# SCH.net
KiCad netlist of a schematic drawn in Altium Designer
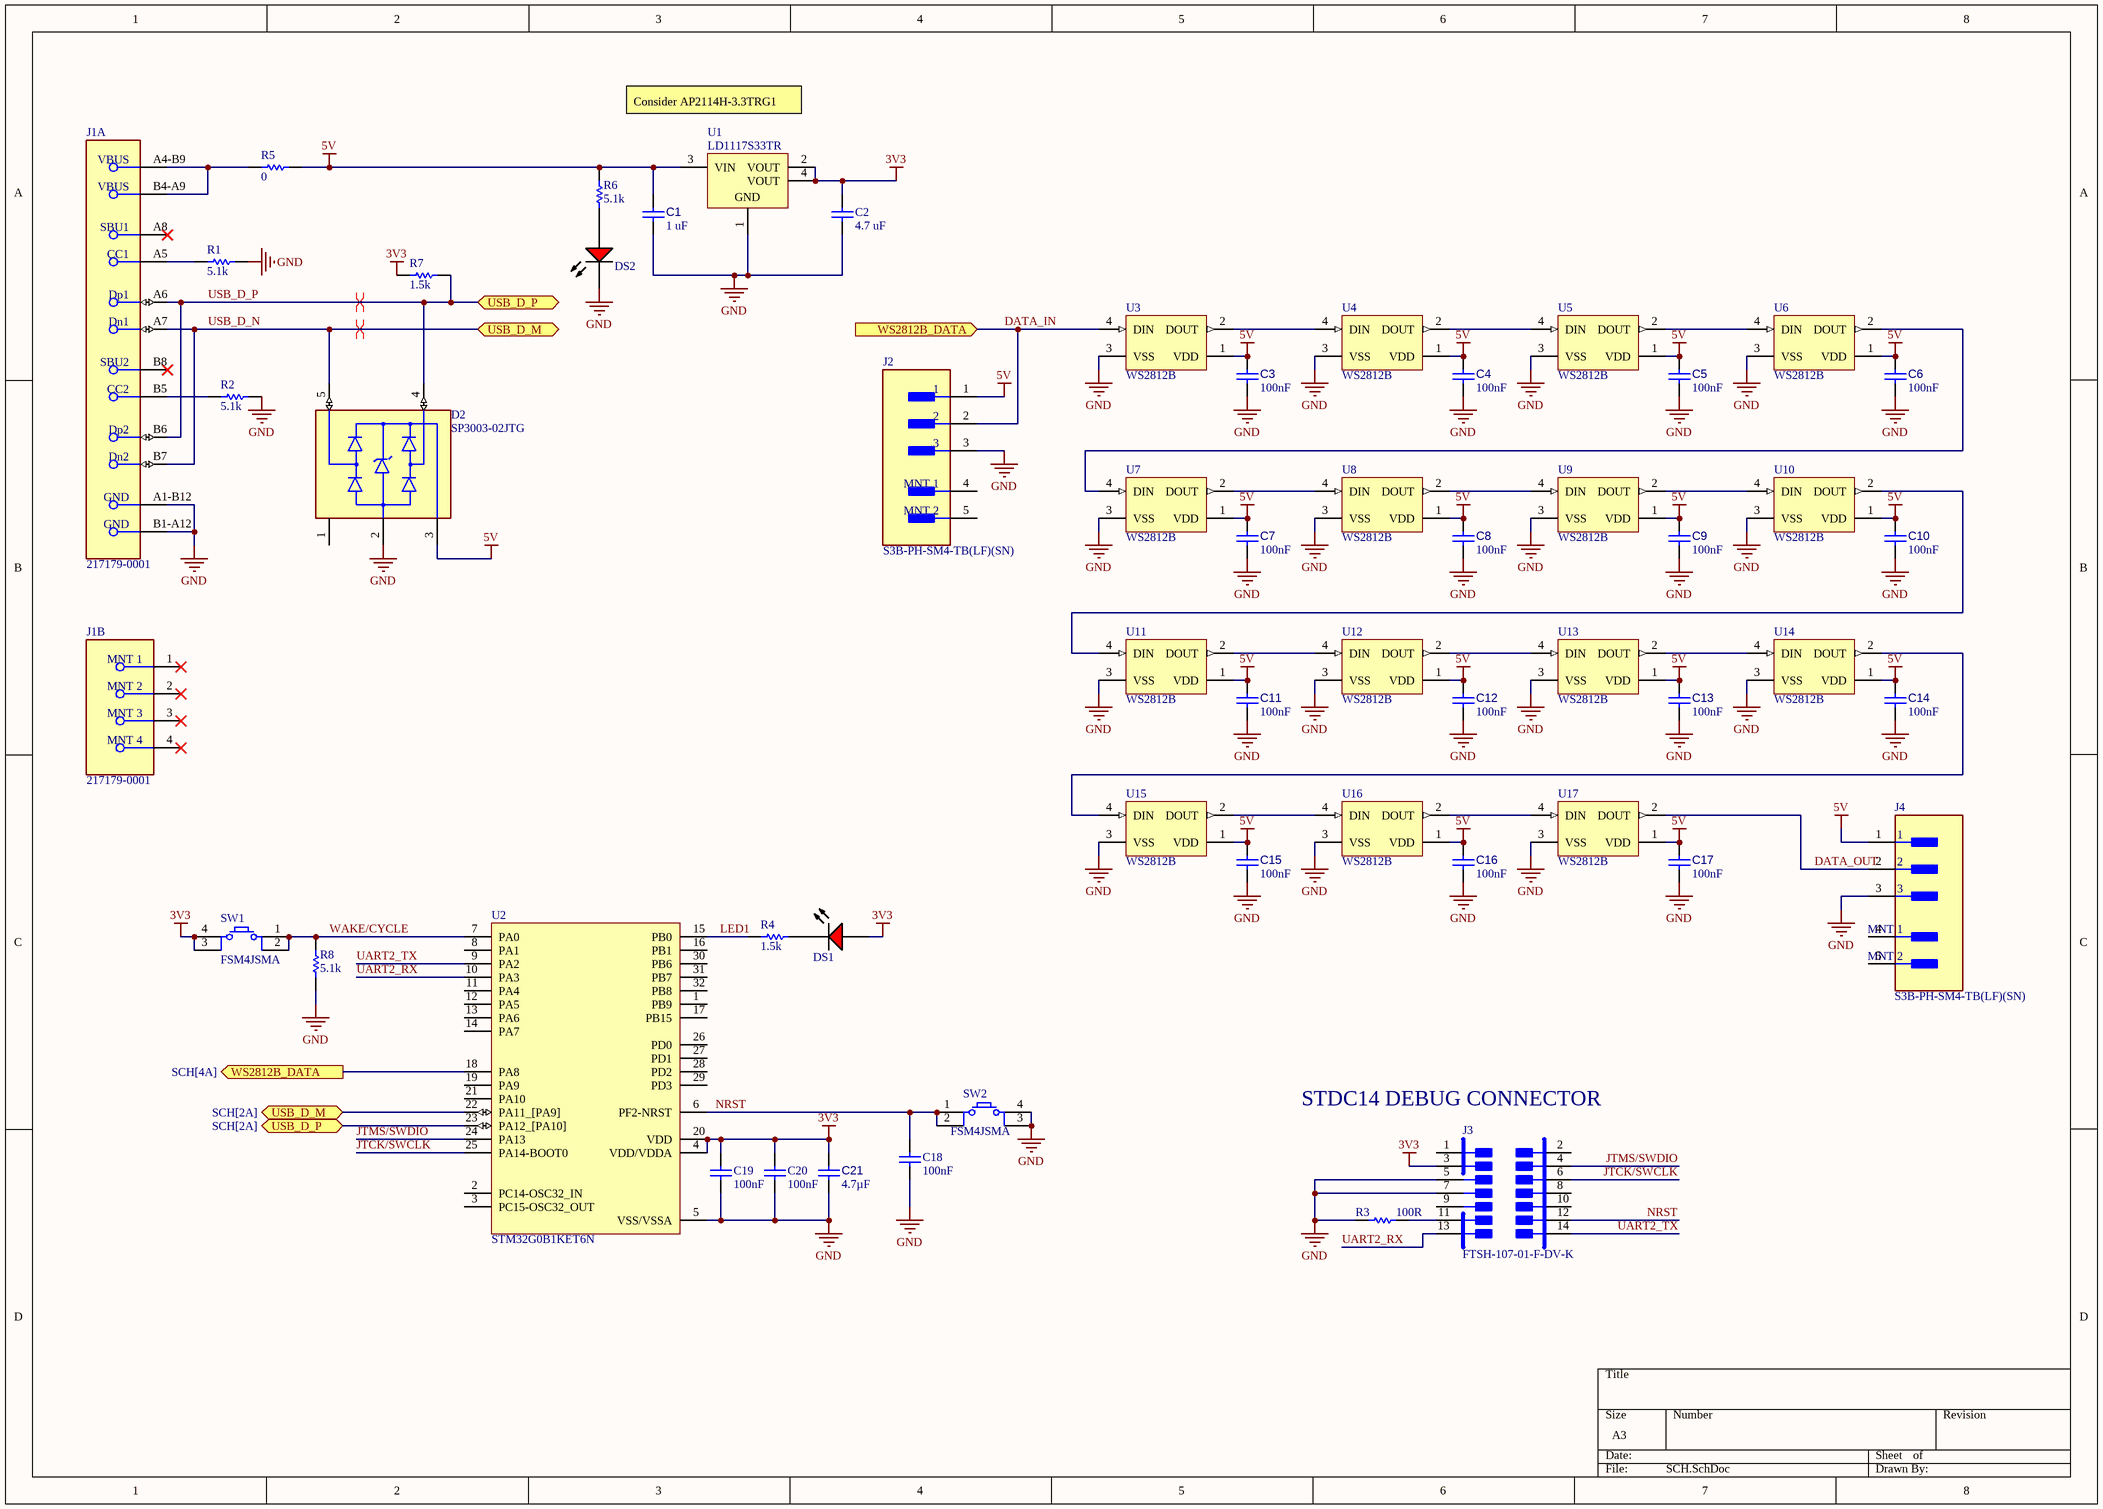
[diagram p0: SCH.SchDoc]

(export (version "E")
  (design (tool "Eeschema 10.0.6"))
  (components
    (comp (ref "C1")
      (value "1 uF")
      (footprint "CAPC3216X19M")
      (description "CAP CER 1UF 100V X7R 1206")
      (fields (field (name "TOLERANCE") "+/-10%") (field (name "Comment") "Capacitor 1 uF +/-10% 100V 1206"))
      (libsource (lib "Dalhousie Formula SAE") (part "CAP-NP-2"))
    )
    (comp (ref "C2")
      (value "4.7 uF")
      (footprint "CAPC3216X19M")
      (description "CAP CER 4.7UF 50V X7R 1206")
      (fields (field (name "TOLERANCE") "+/-10%") (field (name "Comment") "Capacitor 4.7 uF +/-10% 50V 1206"))
      (libsource (lib "Dalhousie Formula SAE") (part "CAP-NP-2"))
    )
    (comp (ref "C3")
      (value "100nF")
      (footprint "CAPC1609X09M")
      (description "CAP CER 0.1UF 50V X7R 0603")
      (fields (field (name "TOLERANCE") "10%") (field (name "Comment") "Capacitor 0.1 uF 10 % 50V 0603"))
      (libsource (lib "Dalhousie Formula SAE") (part "CAP-NP-2"))
    )
    (comp (ref "C4")
      (value "100nF")
      (footprint "CAPC1609X09M")
      (description "CAP CER 0.1UF 50V X7R 0603")
      (fields (field (name "TOLERANCE") "10%") (field (name "Comment") "Capacitor 0.1 uF 10 % 50V 0603"))
      (libsource (lib "Dalhousie Formula SAE") (part "CAP-NP-2"))
    )
    (comp (ref "C5")
      (value "100nF")
      (footprint "CAPC1609X09M")
      (description "CAP CER 0.1UF 50V X7R 0603")
      (fields (field (name "TOLERANCE") "10%") (field (name "Comment") "Capacitor 0.1 uF 10 % 50V 0603"))
      (libsource (lib "Dalhousie Formula SAE") (part "CAP-NP-2"))
    )
    (comp (ref "C6")
      (value "100nF")
      (footprint "CAPC1609X09M")
      (description "CAP CER 0.1UF 50V X7R 0603")
      (fields (field (name "TOLERANCE") "10%") (field (name "Comment") "Capacitor 0.1 uF 10 % 50V 0603"))
      (libsource (lib "Dalhousie Formula SAE") (part "CAP-NP-2"))
    )
    (comp (ref "C7")
      (value "100nF")
      (footprint "CAPC1609X09M")
      (description "CAP CER 0.1UF 50V X7R 0603")
      (fields (field (name "TOLERANCE") "10%") (field (name "Comment") "Capacitor 0.1 uF 10 % 50V 0603"))
      (libsource (lib "Dalhousie Formula SAE") (part "CAP-NP-2"))
    )
    (comp (ref "C8")
      (value "100nF")
      (footprint "CAPC1609X09M")
      (description "CAP CER 0.1UF 50V X7R 0603")
      (fields (field (name "TOLERANCE") "10%") (field (name "Comment") "Capacitor 0.1 uF 10 % 50V 0603"))
      (libsource (lib "Dalhousie Formula SAE") (part "CAP-NP-2"))
    )
    (comp (ref "C9")
      (value "100nF")
      (footprint "CAPC1609X09M")
      (description "CAP CER 0.1UF 50V X7R 0603")
      (fields (field (name "TOLERANCE") "10%") (field (name "Comment") "Capacitor 0.1 uF 10 % 50V 0603"))
      (libsource (lib "Dalhousie Formula SAE") (part "CAP-NP-2"))
    )
    (comp (ref "C10")
      (value "100nF")
      (footprint "CAPC1609X09M")
      (description "CAP CER 0.1UF 50V X7R 0603")
      (fields (field (name "TOLERANCE") "10%") (field (name "Comment") "Capacitor 0.1 uF 10 % 50V 0603"))
      (libsource (lib "Dalhousie Formula SAE") (part "CAP-NP-2"))
    )
    (comp (ref "C11")
      (value "100nF")
      (footprint "CAPC1609X09M")
      (description "CAP CER 0.1UF 50V X7R 0603")
      (fields (field (name "TOLERANCE") "10%") (field (name "Comment") "Capacitor 0.1 uF 10 % 50V 0603"))
      (libsource (lib "Dalhousie Formula SAE") (part "CAP-NP-2"))
    )
    (comp (ref "C12")
      (value "100nF")
      (footprint "CAPC1609X09M")
      (description "CAP CER 0.1UF 50V X7R 0603")
      (fields (field (name "TOLERANCE") "10%") (field (name "Comment") "Capacitor 0.1 uF 10 % 50V 0603"))
      (libsource (lib "Dalhousie Formula SAE") (part "CAP-NP-2"))
    )
    (comp (ref "C13")
      (value "100nF")
      (footprint "CAPC1609X09M")
      (description "CAP CER 0.1UF 50V X7R 0603")
      (fields (field (name "TOLERANCE") "10%") (field (name "Comment") "Capacitor 0.1 uF 10 % 50V 0603"))
      (libsource (lib "Dalhousie Formula SAE") (part "CAP-NP-2"))
    )
    (comp (ref "C14")
      (value "100nF")
      (footprint "CAPC1609X09M")
      (description "CAP CER 0.1UF 50V X7R 0603")
      (fields (field (name "TOLERANCE") "10%") (field (name "Comment") "Capacitor 0.1 uF 10 % 50V 0603"))
      (libsource (lib "Dalhousie Formula SAE") (part "CAP-NP-2"))
    )
    (comp (ref "C15")
      (value "100nF")
      (footprint "CAPC1609X09M")
      (description "CAP CER 0.1UF 50V X7R 0603")
      (fields (field (name "TOLERANCE") "10%") (field (name "Comment") "Capacitor 0.1 uF 10 % 50V 0603"))
      (libsource (lib "Dalhousie Formula SAE") (part "CAP-NP-2"))
    )
    (comp (ref "C16")
      (value "100nF")
      (footprint "CAPC1609X09M")
      (description "CAP CER 0.1UF 50V X7R 0603")
      (fields (field (name "TOLERANCE") "10%") (field (name "Comment") "Capacitor 0.1 uF 10 % 50V 0603"))
      (libsource (lib "Dalhousie Formula SAE") (part "CAP-NP-2"))
    )
    (comp (ref "C17")
      (value "100nF")
      (footprint "CAPC1609X09M")
      (description "CAP CER 0.1UF 50V X7R 0603")
      (fields (field (name "TOLERANCE") "10%") (field (name "Comment") "Capacitor 0.1 uF 10 % 50V 0603"))
      (libsource (lib "Dalhousie Formula SAE") (part "CAP-NP-2"))
    )
    (comp (ref "C18")
      (value "100nF")
      (footprint "CAPC1609X09M")
      (description "CAP CER 0.1UF 50V X7R 0603")
      (fields (field (name "TOLERANCE") "10%") (field (name "Comment") "Capacitor 0.1 uF 10 % 50V 0603"))
      (libsource (lib "Dalhousie Formula SAE") (part "CAP-NP-2"))
    )
    (comp (ref "C19")
      (value "100nF")
      (footprint "CAPC1609X09M")
      (description "CAP CER 0.1UF 50V X7R 0603")
      (fields (field (name "TOLERANCE") "10%") (field (name "Comment") "Capacitor 0.1 uF 10 % 50V 0603"))
      (libsource (lib "Dalhousie Formula SAE") (part "CAP-NP-2"))
    )
    (comp (ref "C20")
      (value "100nF")
      (footprint "CAPC1609X09M")
      (description "CAP CER 0.1UF 50V X7R 0603")
      (fields (field (name "TOLERANCE") "10%") (field (name "Comment") "Capacitor 0.1 uF 10 % 50V 0603"))
      (libsource (lib "Dalhousie Formula SAE") (part "CAP-NP-2"))
    )
    (comp (ref "C21")
      (value "4.7µF")
      (footprint "CAPC1609X09M")
      (description "CAP CER 4.7UF 35V X5R 0603")
      (fields (field (name "TOLERANCE") "10%") (field (name "Comment") "Capacitor 4.7 uF 10 % 35V 0603"))
      (libsource (lib "Dalhousie Formula SAE") (part "CAP-NP-2"))
    )
    (comp (ref "D2")
      (value "SP3003-02JTG")
      (footprint "FP-SP3003-02JTG-MFG")
      (description "TVS DIODE 6V 15V SC70-5")
      (fields
        (field (name "OCTOPART") "https://octopart.com/sp3003-02jtg-littelfuse-11540566")
        (field (name "MANUFACTURER") "Littelfuse")
      )
      (libsource (lib "Altium Content Vault") (part "04e8c59ec1a98fd1540dbf4f650d9d1"))
    )
    (comp (ref "DS1")
      (value "19-217/R6C-AL1M2VY/3T")
      (footprint "EVRL-0603-2_V")
      (description "Chip LED, Red, 5 V, 25 mA, -40 to 85 degC, 2-Pin SMD (0603), RoHS, Tape and Reel")
      (fields (field (name "MANUFACTURER") "Everlight Electronics"))
      (libsource (lib "Dalhousie Formula SAE") (part "LED-RED-AK-2"))
    )
    (comp (ref "DS2")
      (value "19-217/R6C-AL1M2VY/3T")
      (footprint "EVRL-0603-2_V")
      (description "Chip LED, Red, 5 V, 25 mA, -40 to 85 degC, 2-Pin SMD (0603), RoHS, Tape and Reel")
      (fields (field (name "MANUFACTURER") "Everlight Electronics"))
      (libsource (lib "Dalhousie Formula SAE") (part "LED-RED-AK-2"))
    )
    (comp (ref "J1")
      (value "217179-0001")
      (footprint "FP-2171790001-MFG")
      (description "CONN RCP USB2.0 TYP C 24P SMD RA")
      (libsource (lib "Altium Content Vault") (part "8b86497a633d14b3f74642136fc0ce6"))
    )
    (comp (ref "J2")
      (value "S3B-PH-SM4-TB(LF)(SN)")
      (footprint "FP-S3B-PH-SM4-TB_LF_SN-MFG")
      (description "CONN HEADER SMD R/A 3POS 2MM")
      (libsource (lib "") (part "38689d6f3df0f9b234c6ddcef280d85_1"))
    )
    (comp (ref "J3")
      (value "FTSH-107-01-F-DV-K")
      (footprint "FP-FTSH-107-01-F-DV-K-MFG")
      (libsource (lib "Dalhousie Formula SAE") (part "ab214579d66ef07f87fa9c6f4e4f9ab"))
    )
    (comp (ref "J4")
      (value "S3B-PH-SM4-TB(LF)(SN)")
      (footprint "FP-S3B-PH-SM4-TB_LF_SN-MFG")
      (description "CONN HEADER SMD R/A 3POS 2MM")
      (libsource (lib "Altium Content Vault") (part "38689d6f3df0f9b234c6ddcef280d85"))
    )
    (comp (ref "R1")
      (value "5.1k")
      (footprint "RESC1608X55X25ML10T15")
      (description "0603 (1608 Metric) 1/10 W 5K1 1 Thick Film Chip Resistor")
      (fields (field (name "TOLERANCE") "1%") (field (name "POWER") "100mW"))
      (libsource (lib "Dalhousie Formula SAE") (part "RES-2"))
    )
    (comp (ref "R2")
      (value "5.1k")
      (footprint "RESC1608X55X25ML10T15")
      (description "0603 (1608 Metric) 1/10 W 5K1 1 Thick Film Chip Resistor")
      (fields (field (name "TOLERANCE") "1%") (field (name "POWER") "100mW"))
      (libsource (lib "Dalhousie Formula SAE") (part "RES-2"))
    )
    (comp (ref "R3")
      (value "100R")
      (footprint "RESC1608X55X25ML10T15")
      (description "0603 (1608 Metric) 1/10 W 100R 1 Thick Film Chip Resistor")
      (fields (field (name "POWER") "100mW") (field (name "TOLERANCE") "1%"))
      (libsource (lib "Dalhousie Formula SAE") (part "RES-2"))
    )
    (comp (ref "R4")
      (value "1.5k")
      (footprint "RESC1608X55X25ML10T15")
      (description "0603 (1608 Metric) 1/10 W 1K5 1 Thick Film Chip Resistor")
      (fields (field (name "TOLERANCE") "1%") (field (name "POWER") "100mW"))
      (libsource (lib "Dalhousie Formula SAE") (part "RES-2"))
    )
    (comp (ref "R5")
      (value "0")
      (footprint "RESC3116X70X50ML13T20")
      (description "Jumper 1206 (3216 Metric)")
      (fields (field (name "POWER") "250mW") (field (name "TOLERANCE") "0%"))
      (libsource (lib "Dalhousie Formula SAE") (part "RES-2"))
    )
    (comp (ref "R6")
      (value "5.1k")
      (footprint "RESC1608X55X25ML10T15")
      (description "0603 (1608 Metric) 1/10 W 5K1 1 Thick Film Chip Resistor")
      (fields (field (name "TOLERANCE") "1%") (field (name "POWER") "100mW"))
      (libsource (lib "Dalhousie Formula SAE") (part "RES-2"))
    )
    (comp (ref "R7")
      (value "1.5k")
      (footprint "RESC1608X55X25ML10T15")
      (description "0603 (1608 Metric) 1/10 W 1K5 1 Thick Film Chip Resistor")
      (fields (field (name "TOLERANCE") "1%") (field (name "POWER") "100mW"))
      (libsource (lib "Dalhousie Formula SAE") (part "RES-2"))
    )
    (comp (ref "R8")
      (value "5.1k")
      (footprint "RESC1608X55X25ML10T15")
      (description "0603 (1608 Metric) 1/10 W 5K1 1 Thick Film Chip Resistor")
      (fields (field (name "TOLERANCE") "1%") (field (name "POWER") "100mW"))
      (libsource (lib "Dalhousie Formula SAE") (part "RES-2"))
    )
    (comp (ref "SW1")
      (value "FSM4JSMA")
      (footprint "TECO-FSM4JSMA_V")
      (description "Switch Tactile OFF (ON) SPST Round Button Gull Wing 0.05A 12VDC 1.57N SMD Loose Piece")
      (libsource (lib "Dalhousie Formula SAE") (part "SW-SPST-4_A"))
    )
    (comp (ref "SW2")
      (value "FSM4JSMA")
      (footprint "TECO-FSM4JSMA_V")
      (description "Switch Tactile OFF (ON) SPST Round Button Gull Wing 0.05A 12VDC 1.57N SMD Loose Piece")
      (libsource (lib "Dalhousie Formula SAE") (part "SW-SPST-4_A"))
    )
    (comp (ref "U1")
      (value "LD1117S33TR")
      (footprint "STM-SOT-223_M")
      (fields (field (name "POWER") "12W") (field (name "MANUFACTURER") "STMicroelectronics"))
      (libsource (lib "Dalhousie Formula SAE") (part "STM-LD1117-SOT223-4"))
    )
    (comp (ref "U2")
      (value "STM32G0B1KET6N")
      (footprint "STM32G0B1KET6N-Footprint-1")
      (description "RISC Microcontroller, 32-Bit, FLASH, Cortex-M0+ CPU, 64MHz, CMOS, PQFP32")
      (libsource (lib "Dalhousie Formula SAE") (part "STM32G0B1KET6N-Symbol-1"))
    )
    (comp (ref "U3")
      (value "WS2812B")
      (footprint "ADAI-WS2812B_V")
      (fields (field (name "MANUFACTURER") "Adafruit Industries"))
      (libsource (lib "Dalhousie Formula SAE") (part "ADAI-WS2812B-4"))
    )
    (comp (ref "U4")
      (value "WS2812B")
      (footprint "ADAI-WS2812B_V")
      (fields (field (name "MANUFACTURER") "Adafruit Industries"))
      (libsource (lib "Dalhousie Formula SAE") (part "ADAI-WS2812B-4"))
    )
    (comp (ref "U5")
      (value "WS2812B")
      (footprint "ADAI-WS2812B_V")
      (fields (field (name "MANUFACTURER") "Adafruit Industries"))
      (libsource (lib "Dalhousie Formula SAE") (part "ADAI-WS2812B-4"))
    )
    (comp (ref "U6")
      (value "WS2812B")
      (footprint "ADAI-WS2812B_V")
      (fields (field (name "MANUFACTURER") "Adafruit Industries"))
      (libsource (lib "Dalhousie Formula SAE") (part "ADAI-WS2812B-4"))
    )
    (comp (ref "U7")
      (value "WS2812B")
      (footprint "ADAI-WS2812B_V")
      (fields (field (name "MANUFACTURER") "Adafruit Industries"))
      (libsource (lib "Dalhousie Formula SAE") (part "ADAI-WS2812B-4"))
    )
    (comp (ref "U8")
      (value "WS2812B")
      (footprint "ADAI-WS2812B_V")
      (fields (field (name "MANUFACTURER") "Adafruit Industries"))
      (libsource (lib "Dalhousie Formula SAE") (part "ADAI-WS2812B-4"))
    )
    (comp (ref "U9")
      (value "WS2812B")
      (footprint "ADAI-WS2812B_V")
      (fields (field (name "MANUFACTURER") "Adafruit Industries"))
      (libsource (lib "Dalhousie Formula SAE") (part "ADAI-WS2812B-4"))
    )
    (comp (ref "U10")
      (value "WS2812B")
      (footprint "ADAI-WS2812B_V")
      (fields (field (name "MANUFACTURER") "Adafruit Industries"))
      (libsource (lib "Dalhousie Formula SAE") (part "ADAI-WS2812B-4"))
    )
    (comp (ref "U11")
      (value "WS2812B")
      (footprint "ADAI-WS2812B_V")
      (fields (field (name "MANUFACTURER") "Adafruit Industries"))
      (libsource (lib "Dalhousie Formula SAE") (part "ADAI-WS2812B-4"))
    )
    (comp (ref "U12")
      (value "WS2812B")
      (footprint "ADAI-WS2812B_V")
      (fields (field (name "MANUFACTURER") "Adafruit Industries"))
      (libsource (lib "Dalhousie Formula SAE") (part "ADAI-WS2812B-4"))
    )
    (comp (ref "U13")
      (value "WS2812B")
      (footprint "ADAI-WS2812B_V")
      (fields (field (name "MANUFACTURER") "Adafruit Industries"))
      (libsource (lib "Dalhousie Formula SAE") (part "ADAI-WS2812B-4"))
    )
    (comp (ref "U14")
      (value "WS2812B")
      (footprint "ADAI-WS2812B_V")
      (fields (field (name "MANUFACTURER") "Adafruit Industries"))
      (libsource (lib "Dalhousie Formula SAE") (part "ADAI-WS2812B-4"))
    )
    (comp (ref "U15")
      (value "WS2812B")
      (footprint "ADAI-WS2812B_V")
      (fields (field (name "MANUFACTURER") "Adafruit Industries"))
      (libsource (lib "Dalhousie Formula SAE") (part "ADAI-WS2812B-4"))
    )
    (comp (ref "U16")
      (value "WS2812B")
      (footprint "ADAI-WS2812B_V")
      (fields (field (name "MANUFACTURER") "Adafruit Industries"))
      (libsource (lib "Dalhousie Formula SAE") (part "ADAI-WS2812B-4"))
    )
    (comp (ref "U17")
      (value "WS2812B")
      (footprint "ADAI-WS2812B_V")
      (fields (field (name "MANUFACTURER") "Adafruit Industries"))
      (libsource (lib "Dalhousie Formula SAE") (part "ADAI-WS2812B-4"))
    )
  )
  (nets
    (net (code "1") (name "/DATA_IN") (class "Default")
      (node (ref "J2") (pin "2") (pinfunction "2_2") (pintype "passive"))
      (node (ref "U2") (pin "18") (pinfunction "PA8_18") (pintype "passive"))
      (node (ref "U3") (pin "4") (pinfunction "DIN_4") (pintype "input"))
    )
    (net (code "2") (name "/DATA_OUT") (class "Default")
      (node (ref "J4") (pin "2") (pinfunction "2_2") (pintype "passive"))
      (node (ref "U17") (pin "2") (pinfunction "DOUT_2") (pintype "output"))
    )
    (net (code "3") (name "/JTCK{slash}SWCLK") (class "Default")
      (node (ref "J3") (pin "6") (pinfunction "6_6") (pintype "passive"))
      (node (ref "U2") (pin "25") (pinfunction "PA14-BOOT0_25") (pintype "passive"))
    )
    (net (code "4") (name "/JTMS{slash}SWDIO") (class "Default")
      (node (ref "J3") (pin "4") (pinfunction "4_4") (pintype "passive"))
      (node (ref "U2") (pin "24") (pinfunction "PA13_24") (pintype "passive"))
    )
    (net (code "5") (name "/LED1") (class "Default")
      (node (ref "R4") (pin "2") (pinfunction "2_2") (pintype "passive"))
      (node (ref "U2") (pin "15") (pinfunction "PB0_15") (pintype "passive"))
    )
    (net (code "6") (name "/NRST") (class "Default")
      (node (ref "C18") (pin "2") (pinfunction "2_2") (pintype "passive"))
      (node (ref "J3") (pin "12") (pinfunction "12_12") (pintype "passive"))
      (node (ref "SW2") (pin "1") (pinfunction "1_1") (pintype "passive"))
      (node (ref "SW2") (pin "2") (pinfunction "2_2") (pintype "passive"))
      (node (ref "U2") (pin "6") (pinfunction "PF2-NRST_6") (pintype "passive"))
    )
    (net (code "7") (name "/UART2_RX") (class "Default")
      (node (ref "J3") (pin "13") (pinfunction "13_13") (pintype "passive"))
      (node (ref "U2") (pin "10") (pinfunction "PA3_10") (pintype "passive"))
    )
    (net (code "8") (name "/UART2_TX") (class "Default")
      (node (ref "J3") (pin "14") (pinfunction "14_14") (pintype "passive"))
      (node (ref "U2") (pin "9") (pinfunction "PA2_9") (pintype "passive"))
    )
    (net (code "9") (name "/USB_D_N") (class "Default")
      (node (ref "D2") (pin "5") (pinfunction "I/O1_5") (pintype "bidirectional"))
      (node (ref "J1") (pin "A7") (pinfunction "Dn1_A7") (pintype "bidirectional"))
      (node (ref "J1") (pin "B7") (pinfunction "Dn2_B7") (pintype "bidirectional"))
      (node (ref "U2") (pin "22") (pinfunction "PA11_[PA9]_22") (pintype "bidirectional"))
    )
    (net (code "10") (name "/USB_D_P") (class "Default")
      (node (ref "D2") (pin "4") (pinfunction "I/O2_4") (pintype "bidirectional"))
      (node (ref "J1") (pin "A6") (pinfunction "Dp1_A6") (pintype "bidirectional"))
      (node (ref "J1") (pin "B6") (pinfunction "Dp2_B6") (pintype "bidirectional"))
      (node (ref "R7") (pin "1") (pinfunction "1_1") (pintype "passive"))
      (node (ref "U2") (pin "23") (pinfunction "PA12_[PA10]_23") (pintype "bidirectional"))
    )
    (net (code "11") (name "/WAKE{slash}CYCLE") (class "Default")
      (node (ref "R8") (pin "1") (pinfunction "1_1") (pintype "passive"))
      (node (ref "SW1") (pin "1") (pinfunction "1_1") (pintype "passive"))
      (node (ref "SW1") (pin "2") (pinfunction "2_2") (pintype "passive"))
      (node (ref "U2") (pin "7") (pinfunction "PA0_7") (pintype "passive"))
    )
    (net (code "12") (name "3V3") (class "Default")
      (node (ref "C19") (pin "1") (pinfunction "1_1") (pintype "passive"))
      (node (ref "C2") (pin "2") (pinfunction "2_2") (pintype "passive"))
      (node (ref "C20") (pin "1") (pinfunction "1_1") (pintype "passive"))
      (node (ref "C21") (pin "2") (pinfunction "2_2") (pintype "passive"))
      (node (ref "DS1") (pin "1") (pinfunction "A_1") (pintype "passive"))
      (node (ref "J3") (pin "3") (pinfunction "3_3") (pintype "passive"))
      (node (ref "R7") (pin "2") (pinfunction "2_2") (pintype "passive"))
      (node (ref "SW1") (pin "3") (pinfunction "3_3") (pintype "passive"))
      (node (ref "SW1") (pin "4") (pinfunction "4_4") (pintype "passive"))
      (node (ref "U1") (pin "2") (pinfunction "VOUT_2") (pintype "power_in"))
      (node (ref "U1") (pin "4") (pinfunction "VOUT_4") (pintype "power_in"))
      (node (ref "U2") (pin "20") (pinfunction "VDD_20") (pintype "passive"))
      (node (ref "U2") (pin "4") (pinfunction "VDD/VDDA_4") (pintype "passive"))
    )
    (net (code "13") (name "5V") (class "Default")
      (node (ref "C1") (pin "2") (pinfunction "2_2") (pintype "passive"))
      (node (ref "C10") (pin "2") (pinfunction "2_2") (pintype "passive"))
      (node (ref "C11") (pin "2") (pinfunction "2_2") (pintype "passive"))
      (node (ref "C12") (pin "2") (pinfunction "2_2") (pintype "passive"))
      (node (ref "C13") (pin "2") (pinfunction "2_2") (pintype "passive"))
      (node (ref "C14") (pin "2") (pinfunction "2_2") (pintype "passive"))
      (node (ref "C15") (pin "2") (pinfunction "2_2") (pintype "passive"))
      (node (ref "C16") (pin "2") (pinfunction "2_2") (pintype "passive"))
      (node (ref "C17") (pin "2") (pinfunction "2_2") (pintype "passive"))
      (node (ref "C3") (pin "2") (pinfunction "2_2") (pintype "passive"))
      (node (ref "C4") (pin "2") (pinfunction "2_2") (pintype "passive"))
      (node (ref "C5") (pin "2") (pinfunction "2_2") (pintype "passive"))
      (node (ref "C6") (pin "2") (pinfunction "2_2") (pintype "passive"))
      (node (ref "C7") (pin "2") (pinfunction "2_2") (pintype "passive"))
      (node (ref "C8") (pin "2") (pinfunction "2_2") (pintype "passive"))
      (node (ref "C9") (pin "2") (pinfunction "2_2") (pintype "passive"))
      (node (ref "D2") (pin "3") (pinfunction "VCC_3") (pintype "power_in"))
      (node (ref "J2") (pin "1") (pinfunction "1_1") (pintype "passive"))
      (node (ref "J4") (pin "1") (pinfunction "1_1") (pintype "passive"))
      (node (ref "R5") (pin "2") (pinfunction "2_2") (pintype "passive"))
      (node (ref "R6") (pin "1") (pinfunction "1_1") (pintype "passive"))
      (node (ref "U1") (pin "3") (pinfunction "VIN_3") (pintype "power_in"))
      (node (ref "U10") (pin "1") (pinfunction "VDD_1") (pintype "power_in"))
      (node (ref "U11") (pin "1") (pinfunction "VDD_1") (pintype "power_in"))
      (node (ref "U12") (pin "1") (pinfunction "VDD_1") (pintype "power_in"))
      (node (ref "U13") (pin "1") (pinfunction "VDD_1") (pintype "power_in"))
      (node (ref "U14") (pin "1") (pinfunction "VDD_1") (pintype "power_in"))
      (node (ref "U15") (pin "1") (pinfunction "VDD_1") (pintype "power_in"))
      (node (ref "U16") (pin "1") (pinfunction "VDD_1") (pintype "power_in"))
      (node (ref "U17") (pin "1") (pinfunction "VDD_1") (pintype "power_in"))
      (node (ref "U3") (pin "1") (pinfunction "VDD_1") (pintype "power_in"))
      (node (ref "U4") (pin "1") (pinfunction "VDD_1") (pintype "power_in"))
      (node (ref "U5") (pin "1") (pinfunction "VDD_1") (pintype "power_in"))
      (node (ref "U6") (pin "1") (pinfunction "VDD_1") (pintype "power_in"))
      (node (ref "U7") (pin "1") (pinfunction "VDD_1") (pintype "power_in"))
      (node (ref "U8") (pin "1") (pinfunction "VDD_1") (pintype "power_in"))
      (node (ref "U9") (pin "1") (pinfunction "VDD_1") (pintype "power_in"))
    )
    (net (code "14") (name "GND") (class "Default")
      (node (ref "C1") (pin "1") (pinfunction "1_1") (pintype "passive"))
      (node (ref "C10") (pin "1") (pinfunction "1_1") (pintype "passive"))
      (node (ref "C11") (pin "1") (pinfunction "1_1") (pintype "passive"))
      (node (ref "C12") (pin "1") (pinfunction "1_1") (pintype "passive"))
      (node (ref "C13") (pin "1") (pinfunction "1_1") (pintype "passive"))
      (node (ref "C14") (pin "1") (pinfunction "1_1") (pintype "passive"))
      (node (ref "C15") (pin "1") (pinfunction "1_1") (pintype "passive"))
      (node (ref "C16") (pin "1") (pinfunction "1_1") (pintype "passive"))
      (node (ref "C17") (pin "1") (pinfunction "1_1") (pintype "passive"))
      (node (ref "C18") (pin "1") (pinfunction "1_1") (pintype "passive"))
      (node (ref "C19") (pin "2") (pinfunction "2_2") (pintype "passive"))
      (node (ref "C2") (pin "1") (pinfunction "1_1") (pintype "passive"))
      (node (ref "C20") (pin "2") (pinfunction "2_2") (pintype "passive"))
      (node (ref "C21") (pin "1") (pinfunction "1_1") (pintype "passive"))
      (node (ref "C3") (pin "1") (pinfunction "1_1") (pintype "passive"))
      (node (ref "C4") (pin "1") (pinfunction "1_1") (pintype "passive"))
      (node (ref "C5") (pin "1") (pinfunction "1_1") (pintype "passive"))
      (node (ref "C6") (pin "1") (pinfunction "1_1") (pintype "passive"))
      (node (ref "C7") (pin "1") (pinfunction "1_1") (pintype "passive"))
      (node (ref "C8") (pin "1") (pinfunction "1_1") (pintype "passive"))
      (node (ref "C9") (pin "1") (pinfunction "1_1") (pintype "passive"))
      (node (ref "D2") (pin "2") (pinfunction "GND_2") (pintype "power_in"))
      (node (ref "DS2") (pin "2") (pinfunction "K_2") (pintype "passive"))
      (node (ref "J1") (pin "A1-B12") (pinfunction "GND_A1-B12") (pintype "power_in"))
      (node (ref "J1") (pin "B1-A12") (pinfunction "GND_B1-A12") (pintype "power_in"))
      (node (ref "J2") (pin "3") (pinfunction "3_3") (pintype "passive"))
      (node (ref "J3") (pin "5") (pinfunction "5_5") (pintype "passive"))
      (node (ref "J3") (pin "7") (pinfunction "7_7") (pintype "passive"))
      (node (ref "J4") (pin "3") (pinfunction "3_3") (pintype "passive"))
      (node (ref "R1") (pin "1") (pinfunction "1_1") (pintype "passive"))
      (node (ref "R2") (pin "2") (pinfunction "2_2") (pintype "passive"))
      (node (ref "R3") (pin "1") (pinfunction "1_1") (pintype "passive"))
      (node (ref "R8") (pin "2") (pinfunction "2_2") (pintype "passive"))
      (node (ref "SW2") (pin "3") (pinfunction "3_3") (pintype "passive"))
      (node (ref "SW2") (pin "4") (pinfunction "4_4") (pintype "passive"))
      (node (ref "U1") (pin "1") (pinfunction "GND_1") (pintype "power_in"))
      (node (ref "U10") (pin "3") (pinfunction "VSS_3") (pintype "power_in"))
      (node (ref "U11") (pin "3") (pinfunction "VSS_3") (pintype "power_in"))
      (node (ref "U12") (pin "3") (pinfunction "VSS_3") (pintype "power_in"))
      (node (ref "U13") (pin "3") (pinfunction "VSS_3") (pintype "power_in"))
      (node (ref "U14") (pin "3") (pinfunction "VSS_3") (pintype "power_in"))
      (node (ref "U15") (pin "3") (pinfunction "VSS_3") (pintype "power_in"))
      (node (ref "U16") (pin "3") (pinfunction "VSS_3") (pintype "power_in"))
      (node (ref "U17") (pin "3") (pinfunction "VSS_3") (pintype "power_in"))
      (node (ref "U2") (pin "5") (pinfunction "VSS/VSSA_5") (pintype "passive"))
      (node (ref "U3") (pin "3") (pinfunction "VSS_3") (pintype "power_in"))
      (node (ref "U4") (pin "3") (pinfunction "VSS_3") (pintype "power_in"))
      (node (ref "U5") (pin "3") (pinfunction "VSS_3") (pintype "power_in"))
      (node (ref "U6") (pin "3") (pinfunction "VSS_3") (pintype "power_in"))
      (node (ref "U7") (pin "3") (pinfunction "VSS_3") (pintype "power_in"))
      (node (ref "U8") (pin "3") (pinfunction "VSS_3") (pintype "power_in"))
      (node (ref "U9") (pin "3") (pinfunction "VSS_3") (pintype "power_in"))
    )
    (net (code "15") (name "Net-(DS1-K)") (class "Default")
      (node (ref "DS1") (pin "2") (pinfunction "K_2") (pintype "passive"))
      (node (ref "R4") (pin "1") (pinfunction "1_1") (pintype "passive"))
    )
    (net (code "16") (name "Net-(DS2-A)") (class "Default")
      (node (ref "DS2") (pin "1") (pinfunction "A_1") (pintype "passive"))
      (node (ref "R6") (pin "2") (pinfunction "2_2") (pintype "passive"))
    )
    (net (code "17") (name "Net-(J1A-CC1)") (class "Default")
      (node (ref "J1") (pin "A5") (pinfunction "CC1_A5") (pintype "passive"))
      (node (ref "R1") (pin "2") (pinfunction "2_2") (pintype "passive"))
    )
    (net (code "18") (name "Net-(J1A-CC2)") (class "Default")
      (node (ref "J1") (pin "B5") (pinfunction "CC2_B5") (pintype "passive"))
      (node (ref "R2") (pin "1") (pinfunction "1_1") (pintype "passive"))
    )
    (net (code "19") (name "Net-(J1A-VBUS-PadA4-B9)") (class "Default")
      (node (ref "J1") (pin "A4-B9") (pinfunction "VBUS_A4-B9") (pintype "power_in"))
      (node (ref "J1") (pin "B4-A9") (pinfunction "VBUS_B4-A9") (pintype "power_in"))
      (node (ref "R5") (pin "1") (pinfunction "1_1") (pintype "passive"))
    )
    (net (code "20") (name "Net-(J3-Pad11)") (class "Default")
      (node (ref "J3") (pin "11") (pinfunction "11_11") (pintype "passive"))
      (node (ref "R3") (pin "2") (pinfunction "2_2") (pintype "passive"))
    )
    (net (code "21") (name "Net-(U3-DOUT)") (class "Default")
      (node (ref "U3") (pin "2") (pinfunction "DOUT_2") (pintype "output"))
      (node (ref "U4") (pin "4") (pinfunction "DIN_4") (pintype "input"))
    )
    (net (code "22") (name "Net-(U4-DOUT)") (class "Default")
      (node (ref "U4") (pin "2") (pinfunction "DOUT_2") (pintype "output"))
      (node (ref "U5") (pin "4") (pinfunction "DIN_4") (pintype "input"))
    )
    (net (code "23") (name "Net-(U5-DOUT)") (class "Default")
      (node (ref "U5") (pin "2") (pinfunction "DOUT_2") (pintype "output"))
      (node (ref "U6") (pin "4") (pinfunction "DIN_4") (pintype "input"))
    )
    (net (code "24") (name "Net-(U6-DOUT)") (class "Default")
      (node (ref "U6") (pin "2") (pinfunction "DOUT_2") (pintype "output"))
      (node (ref "U7") (pin "4") (pinfunction "DIN_4") (pintype "input"))
    )
    (net (code "25") (name "Net-(U7-DOUT)") (class "Default")
      (node (ref "U7") (pin "2") (pinfunction "DOUT_2") (pintype "output"))
      (node (ref "U8") (pin "4") (pinfunction "DIN_4") (pintype "input"))
    )
    (net (code "26") (name "Net-(U8-DOUT)") (class "Default")
      (node (ref "U8") (pin "2") (pinfunction "DOUT_2") (pintype "output"))
      (node (ref "U9") (pin "4") (pinfunction "DIN_4") (pintype "input"))
    )
    (net (code "27") (name "Net-(U10-DIN)") (class "Default")
      (node (ref "U10") (pin "4") (pinfunction "DIN_4") (pintype "input"))
      (node (ref "U9") (pin "2") (pinfunction "DOUT_2") (pintype "output"))
    )
    (net (code "28") (name "Net-(U10-DOUT)") (class "Default")
      (node (ref "U10") (pin "2") (pinfunction "DOUT_2") (pintype "output"))
      (node (ref "U11") (pin "4") (pinfunction "DIN_4") (pintype "input"))
    )
    (net (code "29") (name "Net-(U11-DOUT)") (class "Default")
      (node (ref "U11") (pin "2") (pinfunction "DOUT_2") (pintype "output"))
      (node (ref "U12") (pin "4") (pinfunction "DIN_4") (pintype "input"))
    )
    (net (code "30") (name "Net-(U12-DOUT)") (class "Default")
      (node (ref "U12") (pin "2") (pinfunction "DOUT_2") (pintype "output"))
      (node (ref "U13") (pin "4") (pinfunction "DIN_4") (pintype "input"))
    )
    (net (code "31") (name "Net-(U13-DOUT)") (class "Default")
      (node (ref "U13") (pin "2") (pinfunction "DOUT_2") (pintype "output"))
      (node (ref "U14") (pin "4") (pinfunction "DIN_4") (pintype "input"))
    )
    (net (code "32") (name "Net-(U14-DOUT)") (class "Default")
      (node (ref "U14") (pin "2") (pinfunction "DOUT_2") (pintype "output"))
      (node (ref "U15") (pin "4") (pinfunction "DIN_4") (pintype "input"))
    )
    (net (code "33") (name "Net-(U15-DOUT)") (class "Default")
      (node (ref "U15") (pin "2") (pinfunction "DOUT_2") (pintype "output"))
      (node (ref "U16") (pin "4") (pinfunction "DIN_4") (pintype "input"))
    )
    (net (code "34") (name "Net-(U16-DOUT)") (class "Default")
      (node (ref "U16") (pin "2") (pinfunction "DOUT_2") (pintype "output"))
      (node (ref "U17") (pin "4") (pinfunction "DIN_4") (pintype "input"))
    )
    (net (code "35") (name "unconnected-(D2-NC-Pad1)") (class "Default")
      (node (ref "D2") (pin "1") (pinfunction "NC_1") (pintype "passive"))
    )
    (net (code "36") (name "unconnected-(J1A-SBU1-PadA8)") (class "Default")
      (node (ref "J1") (pin "A8") (pinfunction "SBU1_A8") (pintype "passive+no_connect"))
    )
    (net (code "37") (name "unconnected-(J1A-SBU2-PadB8)") (class "Default")
      (node (ref "J1") (pin "B8") (pinfunction "SBU2_B8") (pintype "passive+no_connect"))
    )
    (net (code "38") (name "unconnected-(J1B-MNT_1-Pad1)") (class "Default")
      (node (ref "J1") (pin "1") (pinfunction "MNT_1_1") (pintype "passive+no_connect"))
    )
    (net (code "39") (name "unconnected-(J1B-MNT_2-Pad2)") (class "Default")
      (node (ref "J1") (pin "2") (pinfunction "MNT_2_2") (pintype "passive+no_connect"))
    )
    (net (code "40") (name "unconnected-(J1B-MNT_3-Pad3)") (class "Default")
      (node (ref "J1") (pin "3") (pinfunction "MNT_3_3") (pintype "power_in+no_connect"))
    )
    (net (code "41") (name "unconnected-(J1B-MNT_4-Pad4)") (class "Default")
      (node (ref "J1") (pin "4") (pinfunction "MNT_4_4") (pintype "power_in+no_connect"))
    )
    (net (code "42") (name "unconnected-(J2-MNT_1-Pad4)") (class "Default")
      (node (ref "J2") (pin "4") (pinfunction "MNT_1_4") (pintype "passive"))
    )
    (net (code "43") (name "unconnected-(J2-MNT_2-Pad5)") (class "Default")
      (node (ref "J2") (pin "5") (pinfunction "MNT_2_5") (pintype "passive"))
    )
    (net (code "44") (name "unconnected-(J3-Pad1)") (class "Default")
      (node (ref "J3") (pin "1") (pinfunction "1_1") (pintype "passive"))
    )
    (net (code "45") (name "unconnected-(J3-Pad2)") (class "Default")
      (node (ref "J3") (pin "2") (pinfunction "2_2") (pintype "passive"))
    )
    (net (code "46") (name "unconnected-(J3-Pad8)") (class "Default")
      (node (ref "J3") (pin "8") (pinfunction "8_8") (pintype "passive"))
    )
    (net (code "47") (name "unconnected-(J3-Pad9)") (class "Default")
      (node (ref "J3") (pin "9") (pinfunction "9_9") (pintype "passive"))
    )
    (net (code "48") (name "unconnected-(J3-Pad10)") (class "Default")
      (node (ref "J3") (pin "10") (pinfunction "10_10") (pintype "passive"))
    )
    (net (code "49") (name "unconnected-(J4-MNT_1-Pad4)") (class "Default")
      (node (ref "J4") (pin "4") (pinfunction "MNT_1_4") (pintype "passive"))
    )
    (net (code "50") (name "unconnected-(J4-MNT_2-Pad5)") (class "Default")
      (node (ref "J4") (pin "5") (pinfunction "MNT_2_5") (pintype "passive"))
    )
    (net (code "51") (name "unconnected-(U2-PA1-Pad8)") (class "Default")
      (node (ref "U2") (pin "8") (pinfunction "PA1_8") (pintype "passive"))
    )
    (net (code "52") (name "unconnected-(U2-PA4-Pad11)") (class "Default")
      (node (ref "U2") (pin "11") (pinfunction "PA4_11") (pintype "passive"))
    )
    (net (code "53") (name "unconnected-(U2-PA5-Pad12)") (class "Default")
      (node (ref "U2") (pin "12") (pinfunction "PA5_12") (pintype "passive"))
    )
    (net (code "54") (name "unconnected-(U2-PA6-Pad13)") (class "Default")
      (node (ref "U2") (pin "13") (pinfunction "PA6_13") (pintype "passive"))
    )
    (net (code "55") (name "unconnected-(U2-PA7-Pad14)") (class "Default")
      (node (ref "U2") (pin "14") (pinfunction "PA7_14") (pintype "passive"))
    )
    (net (code "56") (name "unconnected-(U2-PA9-Pad19)") (class "Default")
      (node (ref "U2") (pin "19") (pinfunction "PA9_19") (pintype "passive"))
    )
    (net (code "57") (name "unconnected-(U2-PA10-Pad21)") (class "Default")
      (node (ref "U2") (pin "21") (pinfunction "PA10_21") (pintype "passive"))
    )
    (net (code "58") (name "unconnected-(U2-PB1-Pad16)") (class "Default")
      (node (ref "U2") (pin "16") (pinfunction "PB1_16") (pintype "passive"))
    )
    (net (code "59") (name "unconnected-(U2-PB6-Pad30)") (class "Default")
      (node (ref "U2") (pin "30") (pinfunction "PB6_30") (pintype "passive"))
    )
    (net (code "60") (name "unconnected-(U2-PB7-Pad31)") (class "Default")
      (node (ref "U2") (pin "31") (pinfunction "PB7_31") (pintype "passive"))
    )
    (net (code "61") (name "unconnected-(U2-PB8-Pad32)") (class "Default")
      (node (ref "U2") (pin "32") (pinfunction "PB8_32") (pintype "passive"))
    )
    (net (code "62") (name "unconnected-(U2-PB9-Pad1)") (class "Default")
      (node (ref "U2") (pin "1") (pinfunction "PB9_1") (pintype "passive"))
    )
    (net (code "63") (name "unconnected-(U2-PB15-Pad17)") (class "Default")
      (node (ref "U2") (pin "17") (pinfunction "PB15_17") (pintype "passive"))
    )
    (net (code "64") (name "unconnected-(U2-PC14-OSC32_IN-Pad2)") (class "Default")
      (node (ref "U2") (pin "2") (pinfunction "PC14-OSC32_IN_2") (pintype "passive"))
    )
    (net (code "65") (name "unconnected-(U2-PC15-OSC32_OUT-Pad3)") (class "Default")
      (node (ref "U2") (pin "3") (pinfunction "PC15-OSC32_OUT_3") (pintype "passive"))
    )
    (net (code "66") (name "unconnected-(U2-PD0-Pad26)") (class "Default")
      (node (ref "U2") (pin "26") (pinfunction "PD0_26") (pintype "passive"))
    )
    (net (code "67") (name "unconnected-(U2-PD1-Pad27)") (class "Default")
      (node (ref "U2") (pin "27") (pinfunction "PD1_27") (pintype "passive"))
    )
    (net (code "68") (name "unconnected-(U2-PD2-Pad28)") (class "Default")
      (node (ref "U2") (pin "28") (pinfunction "PD2_28") (pintype "passive"))
    )
    (net (code "69") (name "unconnected-(U2-PD3-Pad29)") (class "Default")
      (node (ref "U2") (pin "29") (pinfunction "PD3_29") (pintype "passive"))
    )
  )
)
